# RF_Antenna.net
KiCad netlist of a schematic drawn in Altium Designer
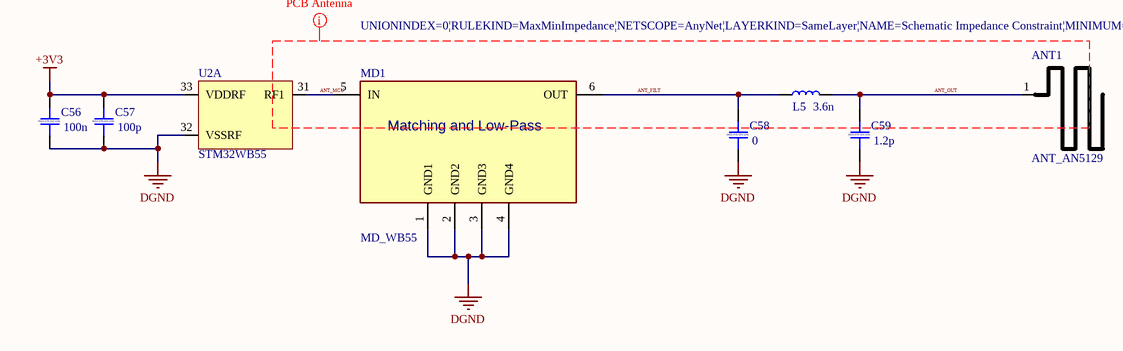
[diagram p0: RF_Antenna.SchDoc]

(export (version "E")
  (design (tool "Eeschema 10.0.6"))
  (components
    (comp (ref "ANT1")
      (value "ANT_AN5129")
      (footprint "ANT_AN5129-Footprint-1")
      (description "PCB Antenna from ST AN5129")
      (libsource (lib "Leonhard Waibl") (part "ANT_AN5129"))
    )
    (comp (ref "C56")
      (value "100n")
      (footprint "CAP_0603")
      (description "Capacitor SMD 0603")
      (fields (field (name "SOURCE") "Schematic-Lib-PhilsLab.SchLib"))
      (libsource (lib "Leonhard Waibl") (part "CAP_EL_NP_5MM"))
    )
    (comp (ref "C57")
      (value "100p")
      (footprint "CAP_0603")
      (description "Capacitor SMD 0603")
      (fields (field (name "SOURCE") "Schematic-Lib-PhilsLab.SchLib"))
      (libsource (lib "Leonhard Waibl") (part "CAP_EL_NP_5MM"))
    )
    (comp (ref "C58")
      (value "0")
      (footprint "CAP_0603")
      (description "Capacitor SMD 0603")
      (fields (field (name "SOURCE") "Schematic-Lib-PhilsLab.SchLib"))
      (libsource (lib "Leonhard Waibl") (part "CAP_EL_NP_5MM"))
    )
    (comp (ref "C59")
      (value "1.2p")
      (footprint "CAP_0603")
      (description "Capacitor SMD 0603")
      (fields (field (name "SOURCE") "Schematic-Lib-PhilsLab.SchLib"))
      (libsource (lib "Leonhard Waibl") (part "CAP_EL_NP_5MM"))
    )
    (comp (ref "L5")
      (value "3.6n")
      (footprint "IND_0603")
      (description "Inductor SMD 0603")
      (fields (field (name "SOURCE") "Schematic-Lib-PhilsLab.SchLib"))
      (libsource (lib "Leonhard Waibl") (part "ASPI-0630HI-6R8M-T15"))
    )
    (comp (ref "MD1")
      (value "MD_WB55")
      (footprint "FP-MLPF-WB55-01E3-MFG")
      (description "Low Pass Filter")
      (libsource (lib "Leonhard Waibl") (part "51e28da9fe7b2e4e5e03ac85244eada"))
    )
    (comp (ref "U2")
      (value "STM32WB55")
      (footprint "QFN40P800X800X100_HS-69N")
      (description "Multiprotocol wireless 32-bit MCU Arm®-based Cortex®-M4")
      (libsource (lib "Leonhard Waibl") (part "STM32WBxx_QFN68"))
    )
  )
  (nets
    (net (code "1") (name "+3V3") (class "Default")
      (node (ref "C56") (pin "1") (pinfunction "1_1") (pintype "passive"))
      (node (ref "C57") (pin "1") (pinfunction "1_1") (pintype "passive"))
      (node (ref "U2") (pin "33") (pinfunction "VDDRF_33") (pintype "passive"))
    )
    (net (code "2") (name "/ANT_FILT") (class "Default")
      (node (ref "C58") (pin "1") (pinfunction "1_1") (pintype "passive"))
      (node (ref "L5") (pin "1") (pinfunction "1_1") (pintype "passive"))
      (node (ref "MD1") (pin "6") (pinfunction "OUT_6") (pintype "passive"))
    )
    (net (code "3") (name "/ANT_MCU") (class "Default")
      (node (ref "MD1") (pin "5") (pinfunction "IN_5") (pintype "power_in"))
      (node (ref "U2") (pin "31") (pinfunction "RF1_31") (pintype "passive"))
    )
    (net (code "4") (name "/ANT_OUT") (class "Default")
      (node (ref "ANT1") (pin "1") (pinfunction "1_1") (pintype "passive"))
      (node (ref "C59") (pin "1") (pinfunction "1_1") (pintype "passive"))
      (node (ref "L5") (pin "2") (pinfunction "2_2") (pintype "passive"))
    )
    (net (code "5") (name "DGND") (class "Default")
      (node (ref "C56") (pin "2") (pinfunction "2_2") (pintype "passive"))
      (node (ref "C57") (pin "2") (pinfunction "2_2") (pintype "passive"))
      (node (ref "C58") (pin "2") (pinfunction "2_2") (pintype "passive"))
      (node (ref "C59") (pin "2") (pinfunction "2_2") (pintype "passive"))
      (node (ref "MD1") (pin "1") (pinfunction "GND1_1") (pintype "power_in"))
      (node (ref "MD1") (pin "2") (pinfunction "GND2_2") (pintype "power_in"))
      (node (ref "MD1") (pin "3") (pinfunction "GND3_3") (pintype "power_in"))
      (node (ref "MD1") (pin "4") (pinfunction "GND4_4") (pintype "power_in"))
      (node (ref "U2") (pin "32") (pinfunction "VSSRF_32") (pintype "passive"))
    )
  )
)
